# RF_FRONTEND.net
KiCad netlist of a schematic drawn in Altium Designer
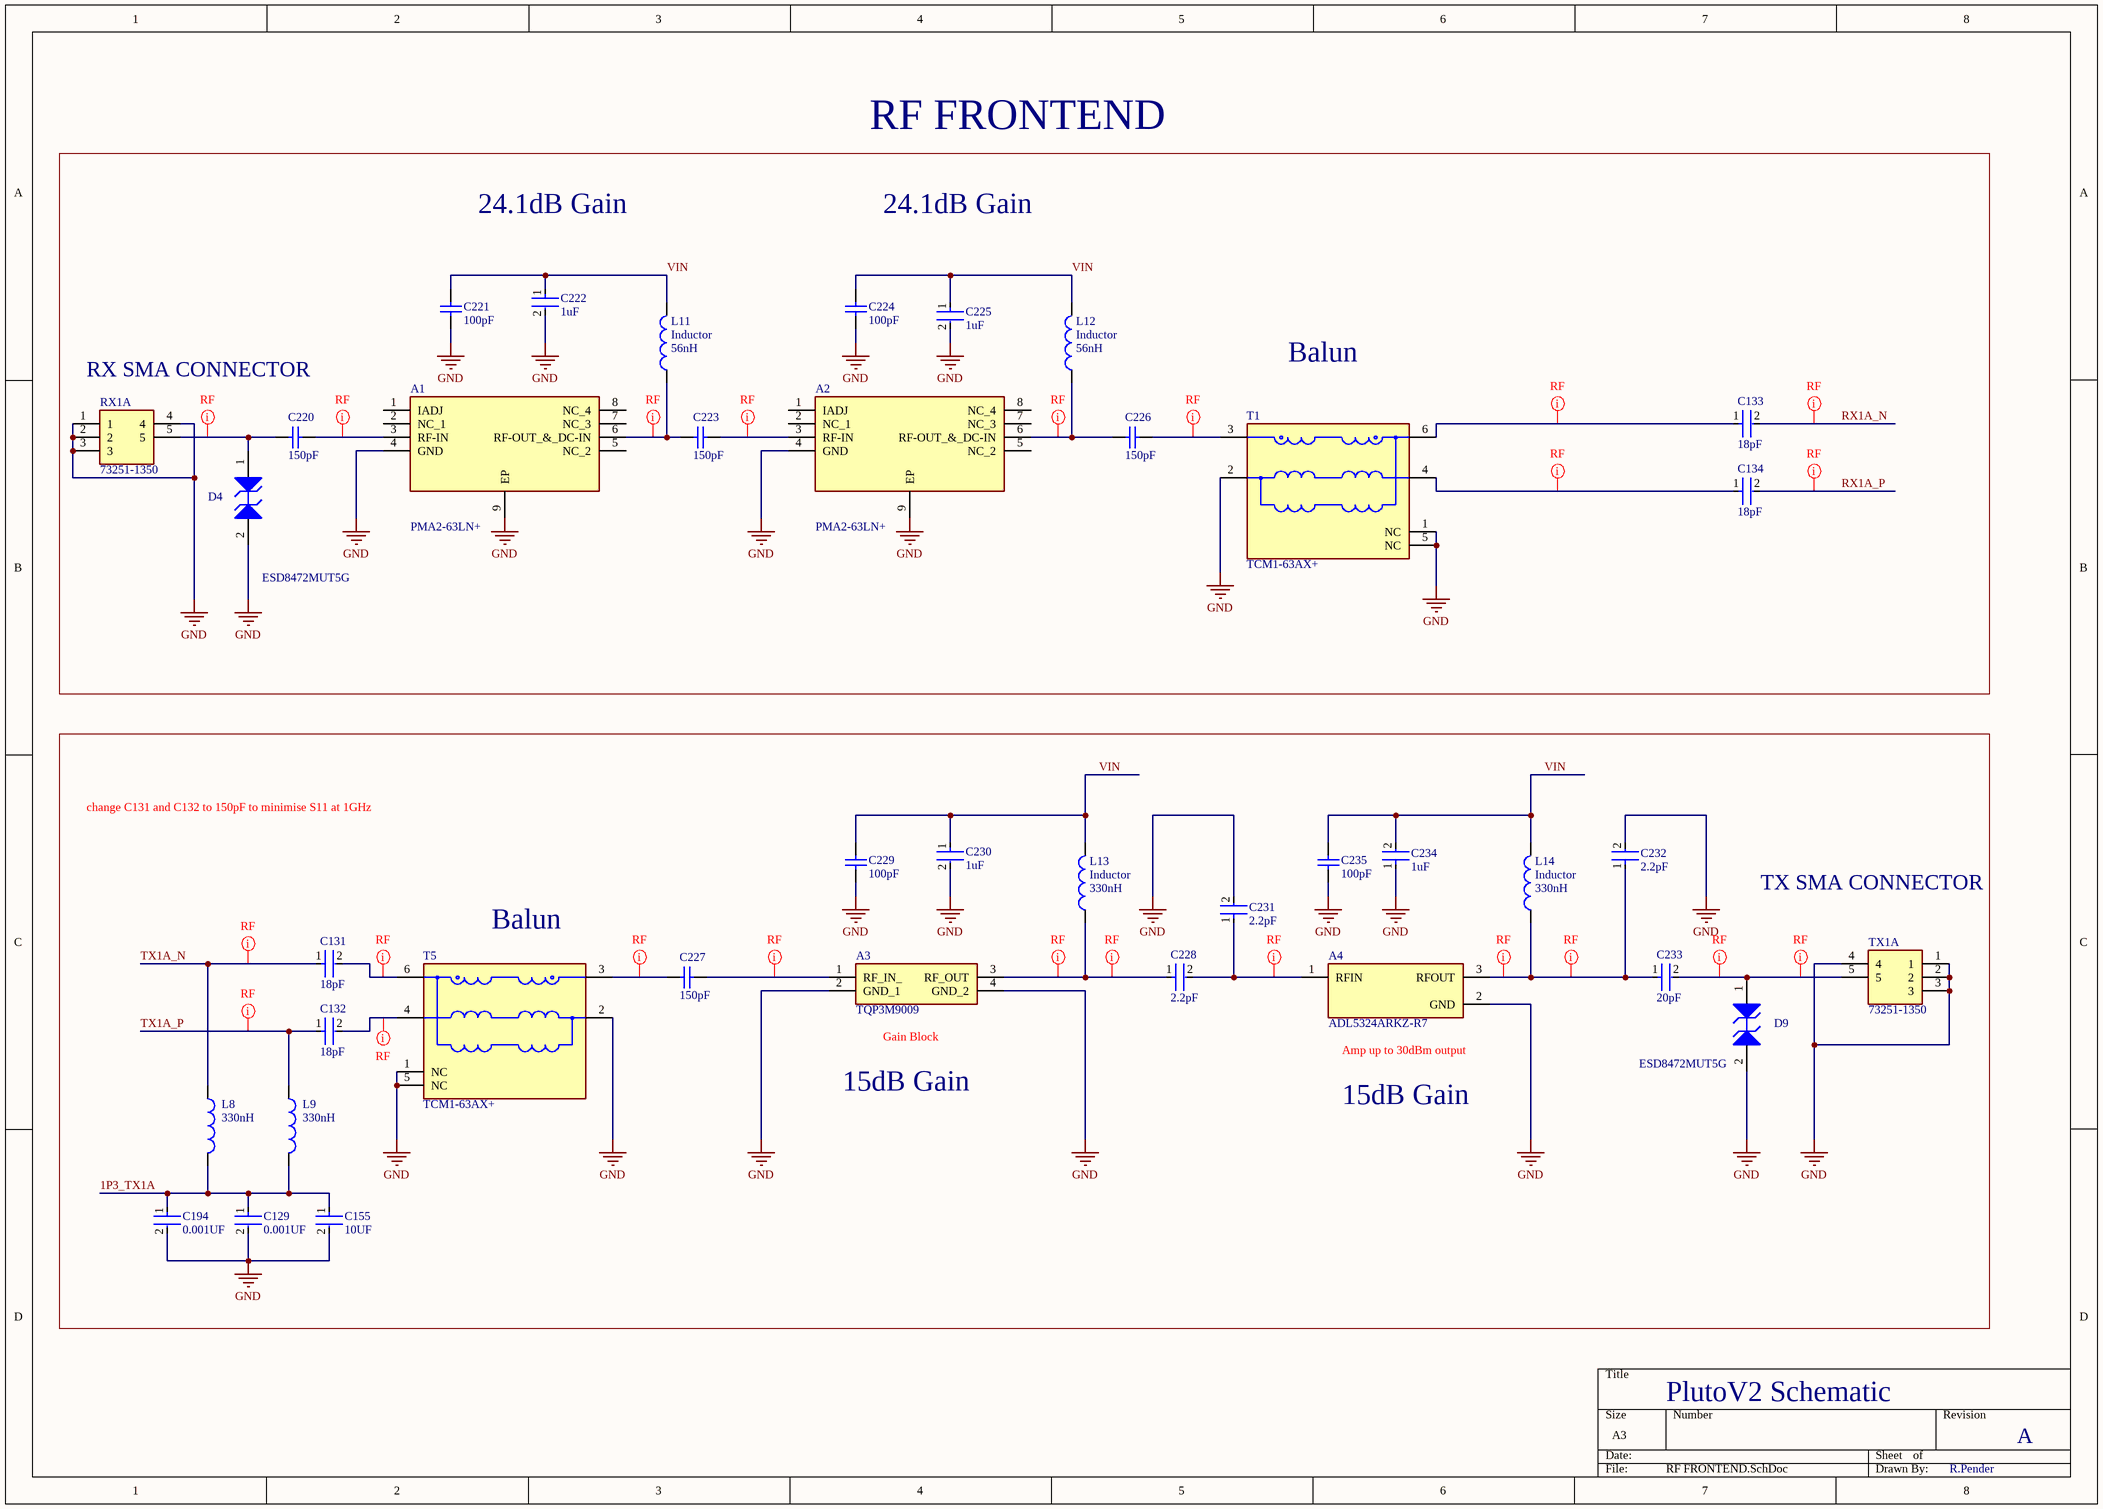
[diagram p0: RF FRONTEND.SchDoc]

(export (version "E")
  (design (tool "Eeschema 10.0.6"))
  (components
    (comp (ref "A1")
      (value "PMA2-63LN+")
      (footprint "SamacSys:SON50P200X200X105-9N")
      (description "Integrated Circuit")
      (libsource (lib "SamacSys") (part "PMA2-63LN+"))
    )
    (comp (ref "A2")
      (value "PMA2-63LN+")
      (footprint "SamacSys:SON50P200X200X105-9N")
      (description "Integrated Circuit")
      (libsource (lib "SamacSys") (part "PMA2-63LN+"))
    )
    (comp (ref "A3")
      (value "TQP3M9009")
      (footprint "SamacSys:TQP3M9009")
      (description "Integrated Circuit")
      (libsource (lib "SamacSys") (part "TQP3M9009"))
    )
    (comp (ref "A4")
      (value "ADL5324ARKZ-R7")
      (footprint "FP-RK-3-MFG")
      (description "IC AMP ISM 400MHZ-4GHZ SOT89-3")
      (libsource (lib "Altium Content Vault") (part "049cc02af2bdf6ac426b0910cff47dc"))
    )
    (comp (ref "C129")
      (value "0.001UF")
      (footprint "FP-GRM033-0_03-MFG")
      (description "Chip Multilayer Ceramic Capacitors for General Purpose, 0201, 1000pF, X7R, 15%, 10%, 25V")
      (fields (field (name "TOLERANCE") "10%") (field (name "VOLTAGE") "25V"))
      (libsource (lib "Altium Content Vault") (part "b4654b650e69147ec39a6b967a45e02"))
    )
    (comp (ref "C131")
      (value "18pF")
      (footprint "FP-GRM033-0_03-IPC_A")
      (description "Chip Multilayer Ceramic Capacitors for General Purpose, 0201, 18pF, C0G, 30ppm/°C, 5%, 50V")
      (fields (field (name "TOLERANCE") "5%") (field (name "VOLTAGE") "50V"))
      (libsource (lib "Altium Content Vault") (part "b4654b650e69147ec39a6b967a45e02"))
    )
    (comp (ref "C132")
      (value "18pF")
      (footprint "FP-GRM033-0_03-IPC_A")
      (description "Chip Multilayer Ceramic Capacitors for General Purpose, 0201, 18pF, C0G, 30ppm/°C, 5%, 50V")
      (fields (field (name "TOLERANCE") "5%") (field (name "VOLTAGE") "50V"))
      (libsource (lib "Altium Content Vault") (part "b4654b650e69147ec39a6b967a45e02"))
    )
    (comp (ref "C133")
      (value "18pF")
      (footprint "FP-GRM033-0_03-IPC_A")
      (description "Chip Multilayer Ceramic Capacitors for General Purpose, 0201, 18pF, C0G, 30ppm/°C, 5%, 50V")
      (fields (field (name "TOLERANCE") "5%") (field (name "VOLTAGE") "50V"))
      (libsource (lib "Altium Content Vault") (part "b4654b650e69147ec39a6b967a45e02"))
    )
    (comp (ref "C134")
      (value "18pF")
      (footprint "FP-GRM033-0_03-IPC_A")
      (description "Chip Multilayer Ceramic Capacitors for General Purpose, 0201, 18pF, C0G, 30ppm/°C, 5%, 50V")
      (fields (field (name "TOLERANCE") "5%") (field (name "VOLTAGE") "50V"))
      (libsource (lib "Altium Content Vault") (part "b4654b650e69147ec39a6b967a45e02"))
    )
    (comp (ref "C155")
      (value "10UF")
      (footprint "FP-GRM188-0_1-e0_2_0_55-IPC_A")
      (description "Chip Multilayer Ceramic Capacitors for General Purpose, 0603, 10uF, X5R, 15%, 20%, 6.3V")
      (fields (field (name "VOLTAGE") "6.3V") (field (name "TOLERANCE") "20%"))
      (libsource (lib "Altium Content Vault") (part "02cd4be3c70576c341d710602a673aa"))
    )
    (comp (ref "C194")
      (value "0.001UF")
      (footprint "FP-GRM033-0_03-MFG")
      (description "Chip Multilayer Ceramic Capacitors for General Purpose, 0201, 1000pF, X7R, 15%, 10%, 25V")
      (fields (field (name "TOLERANCE") "10%") (field (name "VOLTAGE") "25V"))
      (libsource (lib "Altium Content Vault") (part "b4654b650e69147ec39a6b967a45e02"))
    )
    (comp (ref "C220")
      (value "150pF")
      (footprint "CAPC1005X55X25ML05T10")
      (fields (field (name "MANUFACTURER") "Murata") (field (name "PART NUMBER") "GRM1555C1H151JA01D"))
      (libsource (lib "Altium Content Vault") (part "CAP"))
    )
    (comp (ref "C221")
      (value "100pF")
      (footprint "CAPC1005X55X25ML05T10")
      (fields (field (name "MANUFACTURER") "Murata") (field (name "PART NUMBER") "GRM1555C1H101JA01D"))
      (libsource (lib "Altium Content Vault") (part "CAP"))
    )
    (comp (ref "C222")
      (value "1uF")
      (footprint "FP-GRM155-0_05-IPC_B")
      (description "Chip Multilayer Ceramic Capacitors for General Purpose, 0402, 1.0uF, X5R, 15%, 10%, 25V")
      (fields (field (name "VOLTAGE") "25V") (field (name "TOLERANCE") "10%"))
      (libsource (lib "Altium Content Vault") (part "02cd4be3c70576c341d710602a673aa"))
    )
    (comp (ref "C223")
      (value "150pF")
      (footprint "CAPC1005X55X25ML05T10")
      (fields (field (name "MANUFACTURER") "Murata") (field (name "PART NUMBER") "GRM1555C1H151JA01D"))
      (libsource (lib "Altium Content Vault") (part "CAP"))
    )
    (comp (ref "C224")
      (value "100pF")
      (footprint "CAPC1005X55X25ML05T10")
      (fields (field (name "MANUFACTURER") "Murata") (field (name "PART NUMBER") "GRM1555C1H101JA01D"))
      (libsource (lib "Altium Content Vault") (part "CAP"))
    )
    (comp (ref "C225")
      (value "1uF")
      (footprint "FP-GRM155-0_05-IPC_B")
      (description "Chip Multilayer Ceramic Capacitors for General Purpose, 0402, 1.0uF, X5R, 15%, 10%, 25V")
      (fields (field (name "VOLTAGE") "25V") (field (name "TOLERANCE") "10%"))
      (libsource (lib "Altium Content Vault") (part "02cd4be3c70576c341d710602a673aa"))
    )
    (comp (ref "C226")
      (value "150pF")
      (footprint "CAPC1005X55X25ML05T10")
      (fields (field (name "MANUFACTURER") "Murata") (field (name "PART NUMBER") "GRM1555C1H151JA01D"))
      (libsource (lib "Altium Content Vault") (part "CAP"))
    )
    (comp (ref "C227")
      (value "150pF")
      (footprint "CAPC1005X55X25ML05T10")
      (fields (field (name "MANUFACTURER") "Murata") (field (name "PART NUMBER") "GRM1555C1H151JA01D"))
      (libsource (lib "Altium Content Vault") (part "CAP"))
    )
    (comp (ref "C228")
      (value "2.2pF")
      (footprint "FP-GJM155-0_05-MFG")
      (description "Multi-Layer Ceramic Capacitor 2.2pF C0G  ±0.1pF 0402 Paper T/R")
      (fields (field (name "VOLTAGE") "50V"))
      (libsource (lib "Altium Content Vault") (part "02cd4be3c70576c341d710602a673aa"))
    )
    (comp (ref "C229")
      (value "100pF")
      (footprint "CAPC1005X55X25ML05T10")
      (fields (field (name "MANUFACTURER") "Murata") (field (name "PART NUMBER") "GRM1555C1H101JA01D"))
      (libsource (lib "Altium Content Vault") (part "CAP"))
    )
    (comp (ref "C230")
      (value "1uF")
      (footprint "FP-GRM155-0_05-IPC_B")
      (description "Chip Multilayer Ceramic Capacitors for General Purpose, 0402, 1.0uF, X5R, 15%, 10%, 25V")
      (fields (field (name "VOLTAGE") "25V") (field (name "TOLERANCE") "10%"))
      (libsource (lib "Altium Content Vault") (part "02cd4be3c70576c341d710602a673aa"))
    )
    (comp (ref "C231")
      (value "2.2pF")
      (footprint "FP-GJM155-0_05-MFG")
      (description "Multi-Layer Ceramic Capacitor 2.2pF C0G  ±0.1pF 0402 Paper T/R")
      (fields (field (name "VOLTAGE") "50V"))
      (libsource (lib "Altium Content Vault") (part "02cd4be3c70576c341d710602a673aa"))
    )
    (comp (ref "C232")
      (value "2.2pF")
      (footprint "FP-GJM155-0_05-MFG")
      (description "Multi-Layer Ceramic Capacitor 2.2pF C0G  ±0.1pF 0402 Paper T/R")
      (fields (field (name "VOLTAGE") "50V"))
      (libsource (lib "Altium Content Vault") (part "02cd4be3c70576c341d710602a673aa"))
    )
    (comp (ref "C233")
      (value "20pF")
      (footprint "FP-GJM155-0_05-IPC_C")
      (description "Multi-Layer Ceramic Capacitor 20pF C0G  ±2% 0402 Paper T/R")
      (fields (field (name "TOLERANCE") "2%"))
      (libsource (lib "Altium Content Vault") (part "02cd4be3c70576c341d710602a673aa"))
    )
    (comp (ref "C234")
      (value "1uF")
      (footprint "FP-GRM155-0_05-MFG")
      (description "Chip Multilayer Ceramic Capacitors for General Purpose, 0402, 1.0uF, X5R, 15%, 10%, 25V")
      (fields (field (name "TOLERANCE") "10%"))
      (libsource (lib "Altium Content Vault") (part "02cd4be3c70576c341d710602a673aa"))
    )
    (comp (ref "C235")
      (value "100pF")
      (footprint "CAPC1005X55X25ML05T10")
      (fields (field (name "MANUFACTURER") "Murata") (field (name "PART NUMBER") "GRM1555C1H101JA01D"))
      (libsource (lib "Altium Content Vault") (part "CAP"))
    )
    (comp (ref "D4")
      (value "ESD8472MUT5G")
      (footprint "ONSC-X3DFN-2-152AF-01_V")
      (fields (field (name "MANUFACTURER") "On Semiconductor"))
      (libsource (lib "Altium Content Vault") (part "ONSC-A1A2-2"))
    )
    (comp (ref "D9")
      (value "ESD8472MUT5G")
      (footprint "ONSC-X3DFN-2-152AF-01_V")
      (fields (field (name "MANUFACTURER") "On Semiconductor"))
      (libsource (lib "Altium Content Vault") (part "ONSC-A1A2-2"))
    )
    (comp (ref "L8")
      (value "330nH")
      (footprint "0402-A")
      (description "Inductor")
      (fields (field (name "PUBLISHER") "Altium Limited"))
      (libsource (lib "Miscellaneous Devices") (part "Inductor"))
    )
    (comp (ref "L9")
      (value "330nH")
      (footprint "0402-A")
      (description "Inductor")
      (fields (field (name "PUBLISHER") "Altium Limited"))
      (libsource (lib "Miscellaneous Devices") (part "Inductor"))
    )
    (comp (ref "L11")
      (value "Inductor")
      (footprint "0402-A")
      (fields (field (name "ALTIUM_VALUE") "56nH") (field (name "PUBLISHER") "Altium Limited"))
      (libsource (lib "Miscellaneous Devices") (part "Inductor"))
    )
    (comp (ref "L12")
      (value "Inductor")
      (footprint "0402-A")
      (fields (field (name "ALTIUM_VALUE") "56nH") (field (name "PUBLISHER") "Altium Limited"))
      (libsource (lib "Miscellaneous Devices") (part "Inductor"))
    )
    (comp (ref "L13")
      (value "Inductor")
      (footprint "0402-A")
      (fields (field (name "ALTIUM_VALUE") "330nH") (field (name "PUBLISHER") "Altium Limited"))
      (libsource (lib "Miscellaneous Devices") (part "Inductor"))
    )
    (comp (ref "L14")
      (value "Inductor")
      (footprint "0402-A")
      (fields (field (name "ALTIUM_VALUE") "330nH") (field (name "PUBLISHER") "Altium Limited"))
      (libsource (lib "Miscellaneous Devices") (part "Inductor"))
    )
    (comp (ref "RX1A")
      (value "73251-1350")
      (footprint "SamacSys:73251-1350")
      (description "Connector")
      (libsource (lib "*") (part "73251-1350"))
    )
    (comp (ref "T1")
      (value "TCM1-63AX+")
      (footprint "FP-TCM1-63AX+-MFG")
      (description "1:1 CORE & WIRE Transformer, 10 - 6000 MHz, 50Ω")
      (fields
        (field (name "MANUFACTURER") "Mini-Circuits")
        (field (name "OCTOPART") "https://octopart.com/tcm1-63ax%2B-mini-circuits-107315723")
      )
      (libsource (lib "") (part "572340aedd709dbafee1a1d3331a406_1"))
    )
    (comp (ref "T5")
      (value "TCM1-63AX+")
      (footprint "FP-TCM1-63AX+-MFG")
      (description "1:1 CORE & WIRE Transformer, 10 - 6000 MHz, 50Ω")
      (fields
        (field (name "MANUFACTURER") "Mini-Circuits")
        (field (name "OCTOPART") "https://octopart.com/tcm1-63ax%2B-mini-circuits-107315723")
      )
      (libsource (lib "Altium Content Vault") (part "572340aedd709dbafee1a1d3331a406"))
    )
    (comp (ref "TX1A")
      (value "73251-1350")
      (footprint "SamacSys:73251-1350")
      (description "Connector")
      (libsource (lib "") (part "73251-1350_1"))
    )
  )
  (nets
    (net (code "1") (name "/1P3_TX1A") (class "Default")
      (node (ref "C129") (pin "1") (pinfunction "1_1") (pintype "passive"))
      (node (ref "C155") (pin "1") (pinfunction "1_1") (pintype "passive"))
      (node (ref "C194") (pin "1") (pinfunction "1_1") (pintype "passive"))
      (node (ref "L8") (pin "2") (pinfunction "2_2") (pintype "passive"))
      (node (ref "L9") (pin "2") (pinfunction "2_2") (pintype "passive"))
    )
    (net (code "2") (name "/RX1A_N") (class "Default")
      (node (ref "C133") (pin "2") (pinfunction "2_2") (pintype "passive"))
    )
    (net (code "3") (name "/RX1A_P") (class "Default")
      (node (ref "C134") (pin "2") (pinfunction "2_2") (pintype "passive"))
    )
    (net (code "4") (name "/TX1A_N") (class "Default")
      (node (ref "C131") (pin "1") (pinfunction "1_1") (pintype "passive"))
      (node (ref "L8") (pin "1") (pinfunction "1_1") (pintype "passive"))
    )
    (net (code "5") (name "/TX1A_P") (class "Default")
      (node (ref "C132") (pin "1") (pinfunction "1_1") (pintype "passive"))
      (node (ref "L9") (pin "1") (pinfunction "1_1") (pintype "passive"))
    )
    (net (code "6") (name "/VIN") (class "Default")
      (node (ref "C221") (pin "1") (pinfunction "1_1") (pintype "passive"))
      (node (ref "C222") (pin "1") (pinfunction "1_1") (pintype "passive"))
      (node (ref "C224") (pin "1") (pinfunction "1_1") (pintype "passive"))
      (node (ref "C225") (pin "1") (pinfunction "1_1") (pintype "passive"))
      (node (ref "C229") (pin "1") (pinfunction "1_1") (pintype "passive"))
      (node (ref "C230") (pin "1") (pinfunction "1_1") (pintype "passive"))
      (node (ref "C234") (pin "2") (pinfunction "2_2") (pintype "passive"))
      (node (ref "C235") (pin "2") (pinfunction "2_2") (pintype "passive"))
      (node (ref "L11") (pin "2") (pinfunction "2_2") (pintype "passive"))
      (node (ref "L12") (pin "2") (pinfunction "2_2") (pintype "passive"))
      (node (ref "L13") (pin "2") (pinfunction "2_2") (pintype "passive"))
      (node (ref "L14") (pin "2") (pinfunction "2_2") (pintype "passive"))
    )
    (net (code "7") (name "GND") (class "Default")
      (node (ref "A1") (pin "4") (pinfunction "GND_4") (pintype "passive"))
      (node (ref "A1") (pin "9") (pinfunction "EP_9") (pintype "passive"))
      (node (ref "A2") (pin "4") (pinfunction "GND_4") (pintype "passive"))
      (node (ref "A2") (pin "9") (pinfunction "EP_9") (pintype "passive"))
      (node (ref "A3") (pin "2") (pinfunction "GND_1_2") (pintype "passive"))
      (node (ref "A3") (pin "4") (pinfunction "GND_2_4") (pintype "passive"))
      (node (ref "A4") (pin "2") (pinfunction "GND_2") (pintype "power_in"))
      (node (ref "C129") (pin "2") (pinfunction "2_2") (pintype "passive"))
      (node (ref "C155") (pin "2") (pinfunction "2_2") (pintype "passive"))
      (node (ref "C194") (pin "2") (pinfunction "2_2") (pintype "passive"))
      (node (ref "C221") (pin "2") (pinfunction "2_2") (pintype "passive"))
      (node (ref "C222") (pin "2") (pinfunction "2_2") (pintype "passive"))
      (node (ref "C224") (pin "2") (pinfunction "2_2") (pintype "passive"))
      (node (ref "C225") (pin "2") (pinfunction "2_2") (pintype "passive"))
      (node (ref "C229") (pin "2") (pinfunction "2_2") (pintype "passive"))
      (node (ref "C230") (pin "2") (pinfunction "2_2") (pintype "passive"))
      (node (ref "C231") (pin "2") (pinfunction "2_2") (pintype "passive"))
      (node (ref "C232") (pin "2") (pinfunction "2_2") (pintype "passive"))
      (node (ref "C234") (pin "1") (pinfunction "1_1") (pintype "passive"))
      (node (ref "C235") (pin "1") (pinfunction "1_1") (pintype "passive"))
      (node (ref "D4") (pin "2") (pinfunction "A2_2") (pintype "passive"))
      (node (ref "D9") (pin "2") (pinfunction "A2_2") (pintype "passive"))
      (node (ref "RX1A") (pin "1") (pinfunction "1_1") (pintype "passive"))
      (node (ref "RX1A") (pin "2") (pinfunction "2_2") (pintype "passive"))
      (node (ref "RX1A") (pin "3") (pinfunction "3_3") (pintype "passive"))
      (node (ref "RX1A") (pin "4") (pinfunction "4_4") (pintype "passive"))
      (node (ref "T1") (pin "1") (pinfunction "NC_1") (pintype "passive"))
      (node (ref "T1") (pin "2") (pinfunction "GND_2") (pintype "passive"))
      (node (ref "T1") (pin "5") (pinfunction "NC_5") (pintype "passive"))
      (node (ref "T5") (pin "1") (pinfunction "NC_1") (pintype "passive"))
      (node (ref "T5") (pin "2") (pinfunction "GND_2") (pintype "passive"))
      (node (ref "T5") (pin "5") (pinfunction "NC_5") (pintype "passive"))
      (node (ref "TX1A") (pin "1") (pinfunction "1_1") (pintype "passive"))
      (node (ref "TX1A") (pin "2") (pinfunction "2_2") (pintype "passive"))
      (node (ref "TX1A") (pin "3") (pinfunction "3_3") (pintype "passive"))
      (node (ref "TX1A") (pin "4") (pinfunction "4_4") (pintype "passive"))
    )
    (net (code "8") (name "Net-(A1-RF-IN)") (class "Default")
      (node (ref "A1") (pin "3") (pinfunction "RF-IN_3") (pintype "passive"))
      (node (ref "C220") (pin "2") (pinfunction "2_2") (pintype "passive"))
    )
    (net (code "9") (name "Net-(A1-RF-OUT_&_DC-IN)") (class "Default")
      (node (ref "A1") (pin "6") (pinfunction "RF-OUT_&_DC-IN_6") (pintype "passive"))
      (node (ref "C223") (pin "1") (pinfunction "1_1") (pintype "passive"))
      (node (ref "L11") (pin "1") (pinfunction "1_1") (pintype "passive"))
    )
    (net (code "10") (name "Net-(A2-RF-IN)") (class "Default")
      (node (ref "A2") (pin "3") (pinfunction "RF-IN_3") (pintype "passive"))
      (node (ref "C223") (pin "2") (pinfunction "2_2") (pintype "passive"))
    )
    (net (code "11") (name "Net-(A2-RF-OUT_&_DC-IN)") (class "Default")
      (node (ref "A2") (pin "6") (pinfunction "RF-OUT_&_DC-IN_6") (pintype "passive"))
      (node (ref "C226") (pin "1") (pinfunction "1_1") (pintype "passive"))
      (node (ref "L12") (pin "1") (pinfunction "1_1") (pintype "passive"))
    )
    (net (code "12") (name "Net-(A3-RF_IN_)") (class "Default")
      (node (ref "A3") (pin "1") (pinfunction "RF_IN__1") (pintype "passive"))
      (node (ref "C227") (pin "2") (pinfunction "2_2") (pintype "passive"))
    )
    (net (code "13") (name "Net-(A3-RF_OUT)") (class "Default")
      (node (ref "A3") (pin "3") (pinfunction "RF_OUT_3") (pintype "passive"))
      (node (ref "C228") (pin "1") (pinfunction "1_1") (pintype "passive"))
      (node (ref "L13") (pin "1") (pinfunction "1_1") (pintype "passive"))
    )
    (net (code "14") (name "Net-(A4-RFIN)") (class "Default")
      (node (ref "A4") (pin "1") (pinfunction "RFIN_1") (pintype "passive"))
      (node (ref "C228") (pin "2") (pinfunction "2_2") (pintype "passive"))
      (node (ref "C231") (pin "1") (pinfunction "1_1") (pintype "passive"))
    )
    (net (code "15") (name "Net-(A4-RFOUT)") (class "Default")
      (node (ref "A4") (pin "3") (pinfunction "RFOUT_3") (pintype "passive"))
      (node (ref "C232") (pin "1") (pinfunction "1_1") (pintype "passive"))
      (node (ref "C233") (pin "1") (pinfunction "1_1") (pintype "passive"))
      (node (ref "L14") (pin "1") (pinfunction "1_1") (pintype "passive"))
    )
    (net (code "16") (name "Net-(D4-A1)") (class "Default")
      (node (ref "C220") (pin "1") (pinfunction "1_1") (pintype "passive"))
      (node (ref "D4") (pin "1") (pinfunction "A1_1") (pintype "passive"))
      (node (ref "RX1A") (pin "5") (pinfunction "5_5") (pintype "passive"))
    )
    (net (code "17") (name "Net-(D9-A1)") (class "Default")
      (node (ref "C233") (pin "2") (pinfunction "2_2") (pintype "passive"))
      (node (ref "D9") (pin "1") (pinfunction "A1_1") (pintype "passive"))
      (node (ref "TX1A") (pin "5") (pinfunction "5_5") (pintype "passive"))
    )
    (net (code "18") (name "Net-(T1-PRIMARY_DOT)") (class "Default")
      (node (ref "C226") (pin "2") (pinfunction "2_2") (pintype "passive"))
      (node (ref "T1") (pin "3") (pinfunction "PRIMARY_DOT_3") (pintype "passive"))
    )
    (net (code "19") (name "Net-(T1-SECONDARY)") (class "Default")
      (node (ref "C134") (pin "1") (pinfunction "1_1") (pintype "passive"))
      (node (ref "T1") (pin "4") (pinfunction "SECONDARY_4") (pintype "passive"))
    )
    (net (code "20") (name "Net-(T1-SECONDARY_DOT)") (class "Default")
      (node (ref "C133") (pin "1") (pinfunction "1_1") (pintype "passive"))
      (node (ref "T1") (pin "6") (pinfunction "SECONDARY_DOT_6") (pintype "passive"))
    )
    (net (code "21") (name "Net-(T5-PRIMARY_DOT)") (class "Default")
      (node (ref "C227") (pin "1") (pinfunction "1_1") (pintype "passive"))
      (node (ref "T5") (pin "3") (pinfunction "PRIMARY_DOT_3") (pintype "passive"))
    )
    (net (code "22") (name "Net-(T5-SECONDARY)") (class "Default")
      (node (ref "C132") (pin "2") (pinfunction "2_2") (pintype "passive"))
      (node (ref "T5") (pin "4") (pinfunction "SECONDARY_4") (pintype "passive"))
    )
    (net (code "23") (name "Net-(T5-SECONDARY_DOT)") (class "Default")
      (node (ref "C131") (pin "2") (pinfunction "2_2") (pintype "passive"))
      (node (ref "T5") (pin "6") (pinfunction "SECONDARY_DOT_6") (pintype "passive"))
    )
    (net (code "24") (name "unconnected-(A1-IADJ-Pad1)") (class "Default")
      (node (ref "A1") (pin "1") (pinfunction "IADJ_1") (pintype "passive"))
    )
    (net (code "25") (name "unconnected-(A1-NC_1-Pad2)") (class "Default")
      (node (ref "A1") (pin "2") (pinfunction "NC_1_2") (pintype "passive"))
    )
    (net (code "26") (name "unconnected-(A1-NC_2-Pad5)") (class "Default")
      (node (ref "A1") (pin "5") (pinfunction "NC_2_5") (pintype "passive"))
    )
    (net (code "27") (name "unconnected-(A1-NC_3-Pad7)") (class "Default")
      (node (ref "A1") (pin "7") (pinfunction "NC_3_7") (pintype "passive"))
    )
    (net (code "28") (name "unconnected-(A1-NC_4-Pad8)") (class "Default")
      (node (ref "A1") (pin "8") (pinfunction "NC_4_8") (pintype "passive"))
    )
    (net (code "29") (name "unconnected-(A2-IADJ-Pad1)") (class "Default")
      (node (ref "A2") (pin "1") (pinfunction "IADJ_1") (pintype "passive"))
    )
    (net (code "30") (name "unconnected-(A2-NC_1-Pad2)") (class "Default")
      (node (ref "A2") (pin "2") (pinfunction "NC_1_2") (pintype "passive"))
    )
    (net (code "31") (name "unconnected-(A2-NC_2-Pad5)") (class "Default")
      (node (ref "A2") (pin "5") (pinfunction "NC_2_5") (pintype "passive"))
    )
    (net (code "32") (name "unconnected-(A2-NC_3-Pad7)") (class "Default")
      (node (ref "A2") (pin "7") (pinfunction "NC_3_7") (pintype "passive"))
    )
    (net (code "33") (name "unconnected-(A2-NC_4-Pad8)") (class "Default")
      (node (ref "A2") (pin "8") (pinfunction "NC_4_8") (pintype "passive"))
    )
  )
)
